# Microcontroler.net
KiCad netlist of a schematic drawn in Altium Designer
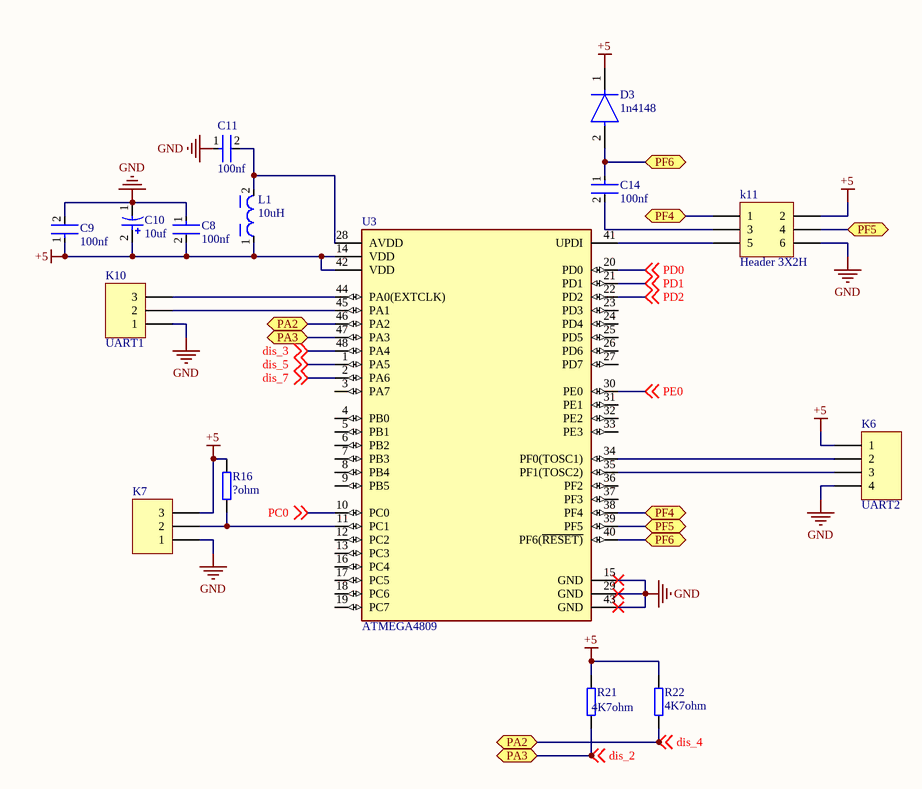
[diagram p0: Microcontroler.SchDoc]

(export (version "E")
  (design (tool "Eeschema 10.0.6"))
  (components
    (comp (ref "C8")
      (value "100nf")
      (footprint "CC_0805_m")
      (fields
        (field (name "MANUFACTURER") "KEMET")
        (field (name "OCTOPART") "https://octopart.com/c0805c224k5ractu-kemet-144670")
        (field (name "MANUFACTURER PART NUMBER") "C0805C224K5RACTU")
      )
      (libsource (lib "Soldeerstation_Final") (part "Capacitor_Ceramic"))
    )
    (comp (ref "C9")
      (value "100nf")
      (footprint "CC_0805_m")
      (fields
        (field (name "MANUFACTURER") "KEMET")
        (field (name "OCTOPART") "https://octopart.com/c0805c224k5ractu-kemet-144670")
        (field (name "MANUFACTURER PART NUMBER") "C0805C224K5RACTU")
      )
      (libsource (lib "Soldeerstation_Final") (part "Capacitor_Ceramic"))
    )
    (comp (ref "C10")
      (value "10uf")
      (footprint "CE_D4_L5,4")
      (fields (field (name "MANUFACTURER") "Panasonic"))
      (libsource (lib "Soldeerstation_Final") (part "Capacitor_Electrolytic"))
    )
    (comp (ref "C11")
      (value "100nf")
      (footprint "CC_0805_m")
      (fields
        (field (name "MANUFACTURER") "KEMET")
        (field (name "OCTOPART") "https://octopart.com/c0805c224k5ractu-kemet-144670")
        (field (name "MANUFACTURER PART NUMBER") "C0805C224K5RACTU")
      )
      (libsource (lib "Soldeerstation_Final") (part "Capacitor_Ceramic"))
    )
    (comp (ref "C14")
      (value "100nf")
      (footprint "CC_0805_m")
      (fields
        (field (name "MANUFACTURER") "KEMET")
        (field (name "OCTOPART") "https://octopart.com/c0805c224k5ractu-kemet-144670")
        (field (name "MANUFACTURER PART NUMBER") "C0805C224K5RACTU")
      )
      (libsource (lib "Soldeerstation_Final") (part "Capacitor_Ceramic"))
    )
    (comp (ref "D3")
      (value "1n4148")
      (footprint "SOD-123FL")
      (fields
        (field (name "MANUFACTURER PART NUMBER") "1N4007")
        (field (name "MANUFACTURER") "Diotec")
        (field (name "OCTOPART") "https://octopart.com/1n4007-diotec-4040411")
      )
      (libsource (lib "Soldeerstation_Final") (part "Diode"))
    )
    (comp (ref "K6")
      (value "UART2")
      (footprint "MHDR1X4")
      (description "Header, 4-Pin, Right Angle")
      (fields (field (name "PUBLISHER") "Altium Limited"))
      (libsource (lib "Miscellaneous Connectors") (part "Header 4H"))
    )
    (comp (ref "K7")
      (value "Header 3H")
      (footprint "MHDR1X3")
      (description "Header, 3-Pin, Right Angle")
      (fields (field (name "PUBLISHER") "Altium Limited"))
      (libsource (lib "Miscellaneous Connectors") (part "Header 3H"))
    )
    (comp (ref "K10")
      (value "UART1")
      (footprint "MHDR1X3")
      (description "Header, 3-Pin, Right Angle")
      (fields (field (name "PUBLISHER") "Altium Limited"))
      (libsource (lib "Miscellaneous Connectors") (part "Header 3H"))
    )
    (comp (ref "k11")
      (value "Header 3X2H")
      (footprint "MHDR2X3")
      (description "Header, 3-Pin, Dual row, Right Angle")
      (fields (field (name "PUBLISHER") "Altium Limited"))
      (libsource (lib "Miscellaneous Connectors") (part "Header 3X2H"))
    )
    (comp (ref "L1")
      (value "10uH")
      (footprint "CC_0805_L")
      (fields (field (name "TOLERANCE") "20%"))
      (libsource (lib "Soldeerstation_Final") (part "Choke"))
    )
    (comp (ref "R16")
      (value "?ohm")
      (footprint "R_0805_M")
      (fields (field (name "MANUFACTURER") "Vishay Dale") (field (name "PART NUMBER") "CRCW08050000Z0EA"))
      (libsource (lib "Soldeerstation_Final") (part "Resistor"))
    )
    (comp (ref "R21")
      (value "4K7ohm")
      (footprint "R_0805_M")
      (fields (field (name "MANUFACTURER") "Vishay Dale") (field (name "PART NUMBER") "CRCW08050000Z0EA"))
      (libsource (lib "Soldeerstation_Final") (part "Resistor"))
    )
    (comp (ref "R22")
      (value "4K7ohm")
      (footprint "R_0805_M")
      (fields (field (name "MANUFACTURER") "Vishay Dale") (field (name "PART NUMBER") "CRCW08050000Z0EA"))
      (libsource (lib "Soldeerstation_Final") (part "Resistor"))
    )
    (comp (ref "U3")
      (value "ATMEGA4809")
      (footprint "TQFP_48_M")
      (libsource (lib "Soldeerstation_Final") (part "ATMEGA4809"))
    )
  )
  (nets
    (net (code "1") (name "+5") (class "Default")
      (node (ref "C10") (pin "2") (pinfunction "2_2") (pintype "passive"))
      (node (ref "C8") (pin "2") (pinfunction "2_2") (pintype "passive"))
      (node (ref "C9") (pin "1") (pinfunction "1_1") (pintype "passive"))
      (node (ref "D3") (pin "1") (pinfunction "C_1") (pintype "passive"))
      (node (ref "K6") (pin "1") (pinfunction "1_1") (pintype "passive"))
      (node (ref "K7") (pin "3") (pinfunction "3_3") (pintype "passive"))
      (node (ref "L1") (pin "1") (pinfunction "1_1") (pintype "passive"))
      (node (ref "R16") (pin "2") (pinfunction "2_2") (pintype "passive"))
      (node (ref "R21") (pin "2") (pinfunction "2_2") (pintype "passive"))
      (node (ref "R22") (pin "2") (pinfunction "2_2") (pintype "passive"))
      (node (ref "U3") (pin "14") (pinfunction "VDD_14") (pintype "power_in"))
      (node (ref "U3") (pin "42") (pinfunction "VDD_42") (pintype "power_in"))
      (node (ref "k11") (pin "2") (pinfunction "2_2") (pintype "passive"))
    )
    (net (code "2") (name "/PF4") (class "Default")
      (node (ref "U3") (pin "38") (pinfunction "PF4_38") (pintype "bidirectional"))
      (node (ref "k11") (pin "1") (pinfunction "1_1") (pintype "passive"))
    )
    (net (code "3") (name "/PF5") (class "Default")
      (node (ref "U3") (pin "39") (pinfunction "PF5_39") (pintype "bidirectional"))
      (node (ref "k11") (pin "4") (pinfunction "4_4") (pintype "passive"))
    )
    (net (code "4") (name "/PF6") (class "Default")
      (node (ref "C14") (pin "1") (pinfunction "1_1") (pintype "passive"))
      (node (ref "D3") (pin "2") (pinfunction "A_2") (pintype "passive"))
      (node (ref "U3") (pin "40") (pinfunction "PF6(~{RESET)}_40") (pintype "bidirectional"))
    )
    (net (code "5") (name "GND") (class "Default")
      (node (ref "C10") (pin "1") (pinfunction "1_1") (pintype "passive"))
      (node (ref "C11") (pin "1") (pinfunction "1_1") (pintype "passive"))
      (node (ref "C8") (pin "1") (pinfunction "1_1") (pintype "passive"))
      (node (ref "C9") (pin "2") (pinfunction "2_2") (pintype "passive"))
      (node (ref "K10") (pin "1") (pinfunction "1_1") (pintype "passive"))
      (node (ref "K6") (pin "4") (pinfunction "4_4") (pintype "passive"))
      (node (ref "K7") (pin "1") (pinfunction "1_1") (pintype "passive"))
      (node (ref "U3") (pin "15") (pinfunction "GND_15") (pintype "open_emitter"))
      (node (ref "U3") (pin "29") (pinfunction "GND_29") (pintype "power_in"))
      (node (ref "U3") (pin "43") (pinfunction "GND_43") (pintype "power_in"))
      (node (ref "k11") (pin "6") (pinfunction "6_6") (pintype "passive"))
    )
    (net (code "6") (name "Net-(C14-Pad2)") (class "Default")
      (node (ref "C14") (pin "2") (pinfunction "2_2") (pintype "passive"))
      (node (ref "k11") (pin "3") (pinfunction "3_3") (pintype "passive"))
    )
    (net (code "7") (name "Net-(U3-AVDD)") (class "Default")
      (node (ref "C11") (pin "2") (pinfunction "2_2") (pintype "passive"))
      (node (ref "L1") (pin "2") (pinfunction "2_2") (pintype "passive"))
      (node (ref "U3") (pin "28") (pinfunction "AVDD_28") (pintype "power_in"))
    )
    (net (code "8") (name "Net-(U3-PA0(EXTCLK))") (class "Default")
      (node (ref "K10") (pin "3") (pinfunction "3_3") (pintype "passive"))
      (node (ref "U3") (pin "44") (pinfunction "PA0(EXTCLK)_44") (pintype "bidirectional"))
    )
    (net (code "9") (name "Net-(U3-PA1)") (class "Default")
      (node (ref "K10") (pin "2") (pinfunction "2_2") (pintype "passive"))
      (node (ref "U3") (pin "45") (pinfunction "PA1_45") (pintype "bidirectional"))
    )
    (net (code "10") (name "Net-(U3-PC1)") (class "Default")
      (node (ref "K7") (pin "2") (pinfunction "2_2") (pintype "passive"))
      (node (ref "R16") (pin "1") (pinfunction "1_1") (pintype "passive"))
      (node (ref "U3") (pin "11") (pinfunction "PC1_11") (pintype "bidirectional"))
    )
    (net (code "11") (name "Net-(U3-PF0(TOSC1))") (class "Default")
      (node (ref "K6") (pin "2") (pinfunction "2_2") (pintype "passive"))
      (node (ref "U3") (pin "34") (pinfunction "PF0(TOSC1)_34") (pintype "bidirectional"))
    )
    (net (code "12") (name "Net-(U3-PF1(TOSC2))") (class "Default")
      (node (ref "K6") (pin "3") (pinfunction "3_3") (pintype "passive"))
      (node (ref "U3") (pin "35") (pinfunction "PF1(TOSC2)_35") (pintype "bidirectional"))
    )
    (net (code "13") (name "Net-(U3-UPDI)") (class "Default")
      (node (ref "U3") (pin "41") (pinfunction "UPDI_41") (pintype "passive"))
      (node (ref "k11") (pin "5") (pinfunction "5_5") (pintype "passive"))
    )
    (net (code "14") (name "PC0") (class "Default")
      (node (ref "U3") (pin "10") (pinfunction "PC0_10") (pintype "bidirectional"))
    )
    (net (code "15") (name "PD0") (class "Default")
      (node (ref "U3") (pin "20") (pinfunction "PD0_20") (pintype "bidirectional"))
    )
    (net (code "16") (name "PD1") (class "Default")
      (node (ref "U3") (pin "21") (pinfunction "PD1_21") (pintype "bidirectional"))
    )
    (net (code "17") (name "PD2") (class "Default")
      (node (ref "U3") (pin "22") (pinfunction "PD2_22") (pintype "bidirectional"))
    )
    (net (code "18") (name "PE0") (class "Default")
      (node (ref "U3") (pin "30") (pinfunction "PE0_30") (pintype "bidirectional"))
    )
    (net (code "19") (name "dis_2") (class "Default")
      (node (ref "R21") (pin "1") (pinfunction "1_1") (pintype "passive"))
      (node (ref "U3") (pin "47") (pinfunction "PA3_47") (pintype "bidirectional"))
    )
    (net (code "20") (name "dis_3") (class "Default")
      (node (ref "U3") (pin "48") (pinfunction "PA4_48") (pintype "bidirectional"))
    )
    (net (code "21") (name "dis_4") (class "Default")
      (node (ref "R22") (pin "1") (pinfunction "1_1") (pintype "passive"))
      (node (ref "U3") (pin "46") (pinfunction "PA2_46") (pintype "bidirectional"))
    )
    (net (code "22") (name "dis_5") (class "Default")
      (node (ref "U3") (pin "1") (pinfunction "PA5_1") (pintype "bidirectional"))
    )
    (net (code "23") (name "dis_7") (class "Default")
      (node (ref "U3") (pin "2") (pinfunction "PA6_2") (pintype "bidirectional"))
    )
    (net (code "24") (name "unconnected-(U3-PA7-Pad3)") (class "Default")
      (node (ref "U3") (pin "3") (pinfunction "PA7_3") (pintype "bidirectional"))
    )
    (net (code "25") (name "unconnected-(U3-PB0-Pad4)") (class "Default")
      (node (ref "U3") (pin "4") (pinfunction "PB0_4") (pintype "bidirectional"))
    )
    (net (code "26") (name "unconnected-(U3-PB1-Pad5)") (class "Default")
      (node (ref "U3") (pin "5") (pinfunction "PB1_5") (pintype "bidirectional"))
    )
    (net (code "27") (name "unconnected-(U3-PB2-Pad6)") (class "Default")
      (node (ref "U3") (pin "6") (pinfunction "PB2_6") (pintype "bidirectional"))
    )
    (net (code "28") (name "unconnected-(U3-PB3-Pad7)") (class "Default")
      (node (ref "U3") (pin "7") (pinfunction "PB3_7") (pintype "bidirectional"))
    )
    (net (code "29") (name "unconnected-(U3-PB4-Pad8)") (class "Default")
      (node (ref "U3") (pin "8") (pinfunction "PB4_8") (pintype "bidirectional"))
    )
    (net (code "30") (name "unconnected-(U3-PB5-Pad9)") (class "Default")
      (node (ref "U3") (pin "9") (pinfunction "PB5_9") (pintype "bidirectional"))
    )
    (net (code "31") (name "unconnected-(U3-PC2-Pad12)") (class "Default")
      (node (ref "U3") (pin "12") (pinfunction "PC2_12") (pintype "bidirectional"))
    )
    (net (code "32") (name "unconnected-(U3-PC3-Pad13)") (class "Default")
      (node (ref "U3") (pin "13") (pinfunction "PC3_13") (pintype "bidirectional"))
    )
    (net (code "33") (name "unconnected-(U3-PC4-Pad16)") (class "Default")
      (node (ref "U3") (pin "16") (pinfunction "PC4_16") (pintype "bidirectional"))
    )
    (net (code "34") (name "unconnected-(U3-PC5-Pad17)") (class "Default")
      (node (ref "U3") (pin "17") (pinfunction "PC5_17") (pintype "bidirectional"))
    )
    (net (code "35") (name "unconnected-(U3-PC6-Pad18)") (class "Default")
      (node (ref "U3") (pin "18") (pinfunction "PC6_18") (pintype "bidirectional"))
    )
    (net (code "36") (name "unconnected-(U3-PC7-Pad19)") (class "Default")
      (node (ref "U3") (pin "19") (pinfunction "PC7_19") (pintype "bidirectional"))
    )
    (net (code "37") (name "unconnected-(U3-PD3-Pad23)") (class "Default")
      (node (ref "U3") (pin "23") (pinfunction "PD3_23") (pintype "bidirectional"))
    )
    (net (code "38") (name "unconnected-(U3-PD4-Pad24)") (class "Default")
      (node (ref "U3") (pin "24") (pinfunction "PD4_24") (pintype "bidirectional"))
    )
    (net (code "39") (name "unconnected-(U3-PD5-Pad25)") (class "Default")
      (node (ref "U3") (pin "25") (pinfunction "PD5_25") (pintype "bidirectional"))
    )
    (net (code "40") (name "unconnected-(U3-PD6-Pad26)") (class "Default")
      (node (ref "U3") (pin "26") (pinfunction "PD6_26") (pintype "bidirectional"))
    )
    (net (code "41") (name "unconnected-(U3-PD7-Pad27)") (class "Default")
      (node (ref "U3") (pin "27") (pinfunction "PD7_27") (pintype "bidirectional"))
    )
    (net (code "42") (name "unconnected-(U3-PE1-Pad31)") (class "Default")
      (node (ref "U3") (pin "31") (pinfunction "PE1_31") (pintype "bidirectional"))
    )
    (net (code "43") (name "unconnected-(U3-PE2-Pad32)") (class "Default")
      (node (ref "U3") (pin "32") (pinfunction "PE2_32") (pintype "bidirectional"))
    )
    (net (code "44") (name "unconnected-(U3-PE3-Pad33)") (class "Default")
      (node (ref "U3") (pin "33") (pinfunction "PE3_33") (pintype "bidirectional"))
    )
    (net (code "45") (name "unconnected-(U3-PF2-Pad36)") (class "Default")
      (node (ref "U3") (pin "36") (pinfunction "PF2_36") (pintype "bidirectional"))
    )
    (net (code "46") (name "unconnected-(U3-PF3-Pad37)") (class "Default")
      (node (ref "U3") (pin "37") (pinfunction "PF3_37") (pintype "bidirectional"))
    )
  )
)
